# Power_regulators.net
KiCad netlist of a schematic drawn in Altium Designer
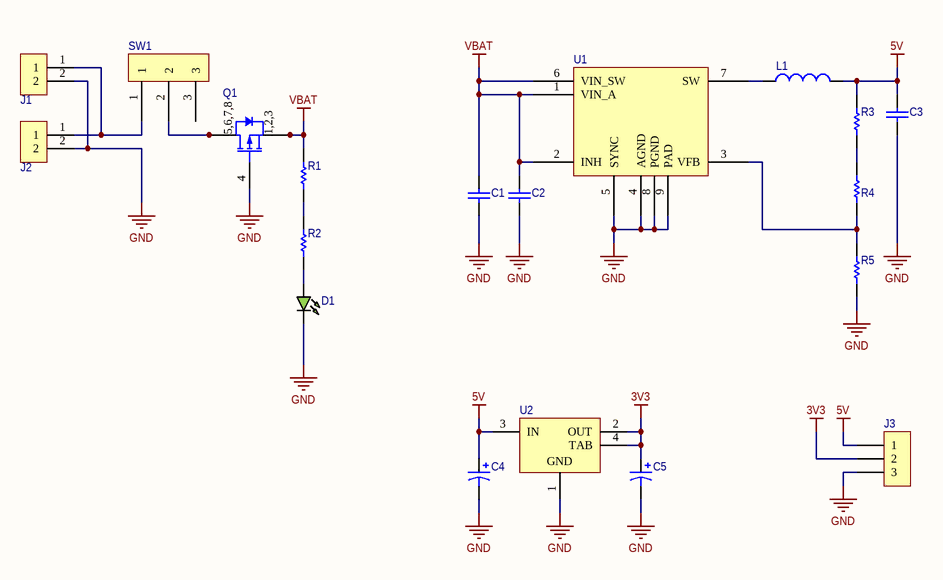
[diagram p0: Power regulators.SchDoc]

(export (version "E")
  (design (tool "Eeschema 10.0.6"))
  (components
    (comp (ref "C1")
      (value "Kemet C1206C475K3RACAUTO")
      (footprint "CAPC3216X180X50ML20T25")
      (description "CAPACITOR, 1206, X7R, 25V, 4.7UF")
      (fields (field (name "MANUFACTURER PART NUMBER") "C1206C475K3RACAUTO"))
      (libsource (lib "Octopart library") (part "CAP-2"))
    )
    (comp (ref "C2")
      (value "Kemet C1206C104K5RACAUTO")
      (footprint "CAPC3216X88X50ML20T25")
      (description "Cap Ceramic 0.1uF 50V X7R 10% SMD 1206 125C Plastic T/R")
      (fields (field (name "MANUFACTURER PART NUMBER") "C1206C104K5RACAUTO"))
      (libsource (lib "Octopart library") (part "CAP-2"))
    )
    (comp (ref "C3")
      (value "Kemet C1210C226K4PAC7800")
      (footprint "CAPC3225X205X50ML20T25")
      (description "Capacitor 1210 22uF 16V")
      (fields (field (name "MANUFACTURER PART NUMBER") "C1210C226K4PACTU"))
      (libsource (lib "Octopart library") (part "CAP-2"))
    )
    (comp (ref "C4")
      (value "Cap Pol2")
      (footprint "PCB-2utroa4rb2vd9is4ckmk-1")
      (description "Cap Tant 10UF 10% 16V 2312")
      (libsource (lib "Octopart library") (part "SYM-bf7b7726339260bc-1"))
    )
    (comp (ref "C5")
      (value "Cap Pol2")
      (footprint "PCB-2utroa4rb2vd9is4ckmk-1")
      (description "Cap Tant 10UF 10% 16V 2312")
      (libsource (lib "Octopart library") (part "SYM-bf7b7726339260bc-1"))
    )
    (comp (ref "D1")
      (value "LTST-C170KGKT")
      (footprint "CHIPLED  0805")
      (description "Green 2 x 1.25 x 1.1 mm 130° Water Clear 35 mcd 2 V Surface Mount LED")
      (fields (field (name "MANUFACTURER") "Lite-On"))
      (libsource (lib "Octopart library") (part "SYM-173fdfefd1b8c8f8-1"))
    )
    (comp (ref "J1")
      (value "TE   647676-2")
      (footprint "PCB-kypnbpwjlxn1m6lvhwgg-1")
      (description "Pluggable terminal block; Colour: green; Mat: PA66; on PCBs; male")
      (fields (field (name "MANUFACTURER PART NUMBER") "15EDGRC-3.5-02P-14"))
      (libsource (lib "Octopart library") (part "SYM-17a5da1f774ec862-1"))
    )
    (comp (ref "J2")
      (value "TE   647676-2")
      (footprint "PCB-kypnbpwjlxn1m6lvhwgg-1")
      (description "Pluggable terminal block; Colour: green; Mat: PA66; on PCBs; male")
      (fields (field (name "MANUFACTURER PART NUMBER") "15EDGRC-3.5-02P-14"))
      (libsource (lib "Octopart library") (part "SYM-17a5da1f774ec862-1"))
    )
    (comp (ref "J3")
      (value "Molex 75757-0431")
      (footprint "Molex 75757-0431")
      (description "Conn Unshrouded Header HDR 3 POS 3.5mm Solder ST Thru-Hole Tube")
      (libsource (lib "CommunityVault") (part "CMP-6ec4a6b2c126b103-1"))
    )
    (comp (ref "L1")
      (value "RLF7030T-3R3M4R1")
      (footprint "INDC7922X32N")
      (description "Inductor Power Shielded Wirewound 3.3uH 20% 100KHz Ferrite 4.1A 20.88mOhm DCR T/R")
      (libsource (lib "Octopart library") (part "SYM-b51a7c1577336add-3"))
    )
    (comp (ref "Q1")
      (value "SYM-000bc976ee97dfcc-1")
      (footprint "PCB-o8kpmntap7p5mqdjohts-1")
      (description "P-Channel 40 V 13 mOhm SMT PowerTrench® Mosfet - SOIC-8")
      (fields (field (name "MANUFACTURER PART NUMBER") "FDS4141"))
      (libsource (lib "Octopart library") (part "SYM-000bc976ee97dfcc-1"))
    )
    (comp (ref "R1")
      (value "Vishay Dale CRCW12061K00FKEB")
      (footprint "RESC3216X60X45ML10T20")
      (description "Thick Film Resistors - SMD 1/4watt 1Kohms 1%")
      (fields (field (name "MANUFACTURER PART NUMBER") "CRCW12061K00FKEB"))
      (libsource (lib "Octopart library") (part "RES-2"))
    )
    (comp (ref "R2")
      (value "Vishay Dale CRCW12061K00FKEB")
      (footprint "RESC3216X60X45ML10T20")
      (description "Thick Film Resistors - SMD 1/4watt 1Kohms 1%")
      (fields (field (name "MANUFACTURER PART NUMBER") "CRCW12061K00FKEB"))
      (libsource (lib "Octopart library") (part "RES-2"))
    )
    (comp (ref "R3")
      (value "Vishay CRCW1206100KFKEA")
      (footprint "PCB-76kjjvsvnrmyxpejc0rn-1")
      (description "Res Thick Film 1206 100K Ohm 1% 1/4W ±100ppm/°C Molded SMD SMD Paper T/R")
      (libsource (lib "Octopart library") (part "SYM-085cc21b0566d79b-7"))
    )
    (comp (ref "R4")
      (value "Vishay Dale CRCW12065K10FKEA")
      (footprint "RESC3216X60X45ML10T20")
      (description "RES SMD 5.1K OHM 1% 1/4W 1206")
      (fields (field (name "MANUFACTURER PART NUMBER") "CRCW12065K10FKEA"))
      (libsource (lib "Octopart library") (part "RES-2"))
    )
    (comp (ref "R5")
      (value "Vishay Dale CRCW120620K0FKTA")
      (footprint "RESC3216X60X45ML10T20")
      (description "RES SMD 20K OHM 1% 1/4W 1206")
      (fields (field (name "MANUFACTURER PART NUMBER") "CRCW120620K0FKTA"))
      (libsource (lib "Octopart library") (part "RES-2"))
    )
    (comp (ref "SW1")
      (value "Canal Components SL19-121")
      (footprint "PCB-btjqrve0936pn890qe86-1")
      (description "Switch: slide; Positions: 2; SPDT; 3A/250VAC; 6A/28VDC; ON-ON")
      (fields (field (name "MANUFACTURER PART NUMBER") "SL19-121"))
      (libsource (lib "Octopart library") (part "SYM-2d08e78b94a7f2cf-1"))
    )
    (comp (ref "U1")
      (value "ST1S10")
      (footprint "PCB-q7tc9tlrfg8r6x64pd1q-1")
      (description "ld1086dt33tr for waterspectr")
      (fields (field (name "MANUFACTURER PART NUMBER") "ST1S10PHR"))
      (libsource (lib "Octopart library") (part "ld1086dt33tr"))
    )
    (comp (ref "U2")
      (value "LM1117IMPX-3.3/NOPB")
      (footprint "MP04A_N")
      (description "800mA Low-Dropout Linear Regulator, 4-pin SOT-223, Pb-Free")
      (libsource (lib "Octopart library") (part "PM-REG-LM1086-SOT4"))
    )
  )
  (nets
    (net (code "1") (name "3V3") (class "Default")
      (node (ref "C5") (pin "1") (pinfunction "1_1") (pintype "passive"))
      (node (ref "J3") (pin "2") (pinfunction "2_2") (pintype "passive"))
      (node (ref "U2") (pin "2") (pinfunction "OUT_2") (pintype "power_in"))
      (node (ref "U2") (pin "4") (pinfunction "TAB_4") (pintype "power_in"))
    )
    (net (code "2") (name "5V") (class "Default")
      (node (ref "C3") (pin "1") (pinfunction "1_1") (pintype "passive"))
      (node (ref "C4") (pin "1") (pinfunction "1_1") (pintype "passive"))
      (node (ref "J3") (pin "1") (pinfunction "1_1") (pintype "passive"))
      (node (ref "L1") (pin "2") (pinfunction "2_2") (pintype "passive"))
      (node (ref "R3") (pin "2") (pinfunction "2_2") (pintype "passive"))
      (node (ref "U2") (pin "3") (pinfunction "IN_3") (pintype "power_in"))
    )
    (net (code "3") (name "GND") (class "Default")
      (node (ref "C1") (pin "2") (pinfunction "2_2") (pintype "passive"))
      (node (ref "C2") (pin "2") (pinfunction "2_2") (pintype "passive"))
      (node (ref "C3") (pin "2") (pinfunction "2_2") (pintype "passive"))
      (node (ref "C4") (pin "2") (pinfunction "2_2") (pintype "passive"))
      (node (ref "C5") (pin "2") (pinfunction "2_2") (pintype "passive"))
      (node (ref "D1") (pin "1") (pinfunction "K_1") (pintype "passive"))
      (node (ref "J1") (pin "2") (pinfunction "2_2") (pintype "passive"))
      (node (ref "J2") (pin "2") (pinfunction "2_2") (pintype "passive"))
      (node (ref "J3") (pin "3") (pinfunction "3_3") (pintype "passive"))
      (node (ref "Q1") (pin "4") (pinfunction "G_4") (pintype "passive"))
      (node (ref "R5") (pin "2") (pinfunction "2_2") (pintype "passive"))
      (node (ref "U1") (pin "4") (pinfunction "AGND_4") (pintype "power_in"))
      (node (ref "U1") (pin "5") (pinfunction "SYNC_5") (pintype "power_in"))
      (node (ref "U1") (pin "8") (pinfunction "PGND_8") (pintype "power_in"))
      (node (ref "U1") (pin "9") (pinfunction "PAD_9") (pintype "power_in"))
      (node (ref "U2") (pin "1") (pinfunction "GND_1") (pintype "power_in"))
    )
    (net (code "4") (name "Net-(D1-A)") (class "Default")
      (node (ref "D1") (pin "2") (pinfunction "A_2") (pintype "passive"))
      (node (ref "R2") (pin "2") (pinfunction "2_2") (pintype "passive"))
    )
    (net (code "5") (name "Net-(J1-Pad1)") (class "Default")
      (node (ref "J1") (pin "1") (pinfunction "1_1") (pintype "passive"))
      (node (ref "J2") (pin "1") (pinfunction "1_1") (pintype "passive"))
      (node (ref "SW1") (pin "1") (pinfunction "1_1") (pintype "passive"))
    )
    (net (code "6") (name "Net-(Q1-D-Pad5)") (class "Default")
      (node (ref "Q1") (pin "5") (pinfunction "D_5") (pintype "passive"))
      (node (ref "Q1") (pin "6") (pinfunction "D_6") (pintype "passive"))
      (node (ref "Q1") (pin "7") (pinfunction "D_7") (pintype "passive"))
      (node (ref "Q1") (pin "8") (pinfunction "D_8") (pintype "passive"))
      (node (ref "SW1") (pin "2") (pinfunction "2_2") (pintype "passive"))
    )
    (net (code "7") (name "Net-(R1-Pad2)") (class "Default")
      (node (ref "R1") (pin "2") (pinfunction "2_2") (pintype "passive"))
      (node (ref "R2") (pin "1") (pinfunction "1_1") (pintype "passive"))
    )
    (net (code "8") (name "Net-(R3-Pad1)") (class "Default")
      (node (ref "R3") (pin "1") (pinfunction "1_1") (pintype "passive"))
      (node (ref "R4") (pin "2") (pinfunction "2_2") (pintype "passive"))
    )
    (net (code "9") (name "Net-(U1-SW)") (class "Default")
      (node (ref "L1") (pin "1") (pinfunction "1_1") (pintype "passive"))
      (node (ref "U1") (pin "7") (pinfunction "SW_7") (pintype "power_in"))
    )
    (net (code "10") (name "Net-(U1-VFB)") (class "Default")
      (node (ref "R4") (pin "1") (pinfunction "1_1") (pintype "passive"))
      (node (ref "R5") (pin "1") (pinfunction "1_1") (pintype "passive"))
      (node (ref "U1") (pin "3") (pinfunction "VFB_3") (pintype "power_in"))
    )
    (net (code "11") (name "VBAT") (class "Default")
      (node (ref "C1") (pin "1") (pinfunction "1_1") (pintype "passive"))
      (node (ref "C2") (pin "1") (pinfunction "1_1") (pintype "passive"))
      (node (ref "Q1") (pin "1") (pinfunction "S_1") (pintype "passive"))
      (node (ref "Q1") (pin "2") (pinfunction "S_2") (pintype "passive"))
      (node (ref "Q1") (pin "3") (pinfunction "S_3") (pintype "passive"))
      (node (ref "R1") (pin "1") (pinfunction "1_1") (pintype "passive"))
      (node (ref "U1") (pin "1") (pinfunction "VIN_A_1") (pintype "power_in"))
      (node (ref "U1") (pin "2") (pinfunction "INH_2") (pintype "power_in"))
      (node (ref "U1") (pin "6") (pinfunction "VIN_SW_6") (pintype "power_in"))
    )
    (net (code "12") (name "unconnected-(SW1-Pad3)") (class "Default")
      (node (ref "SW1") (pin "3") (pinfunction "3_3") (pintype "passive"))
    )
  )
)
